# RTI-Dome-Shutter.net
KiCad netlist of a schematic drawn in EAGLE
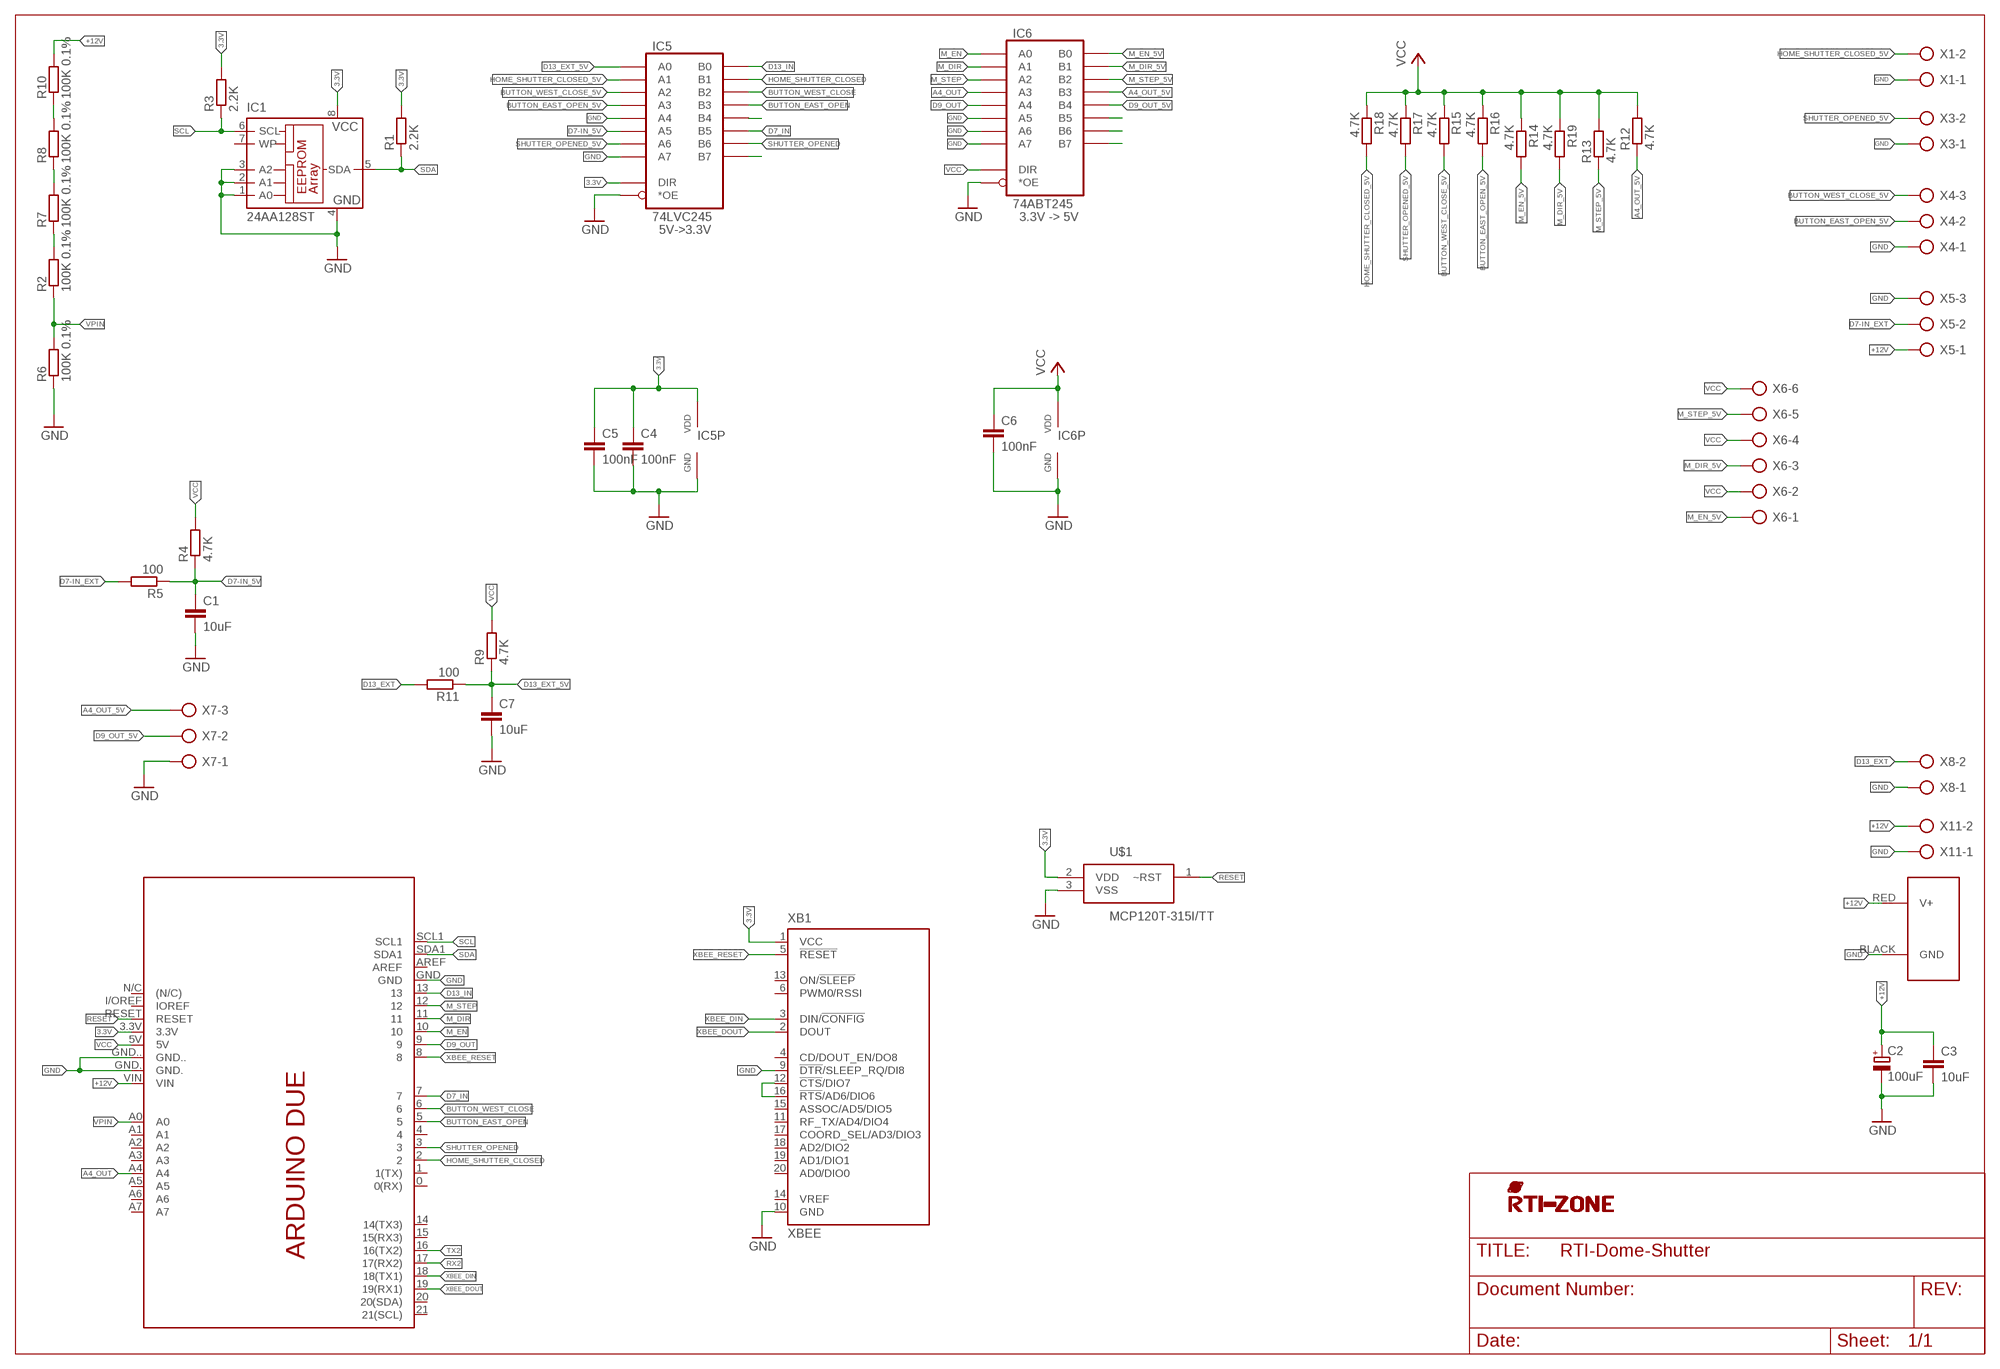
[diagram p0: schematic, sheet 1]

(export (version "E")
  (design (tool "Eeschema 10.0.6"))
  (components
    (comp (ref "C1")
      (value "10uF")
      (footprint "eagle-import:C0805")
      (libsource (lib "eagle-import") (part "C-EU'0805'"))
    )
    (comp (ref "C2")
      (value "100uF")
      (footprint "eagle-import:UD-10X10_NICHICON")
      (libsource (lib "eagle-import") (part "CPOL-EU"))
    )
    (comp (ref "C3")
      (value "10uF")
      (footprint "eagle-import:C0805")
      (libsource (lib "eagle-import") (part "C-EU'0805'"))
    )
    (comp (ref "C4")
      (value "100nF")
      (footprint "eagle-import:C0805")
      (libsource (lib "eagle-import") (part "C-EU'0805'"))
    )
    (comp (ref "C5")
      (value "100nF")
      (footprint "eagle-import:C0805")
      (libsource (lib "eagle-import") (part "C-EU'0805'"))
    )
    (comp (ref "C6")
      (value "100nF")
      (footprint "eagle-import:C0805")
      (libsource (lib "eagle-import") (part "C-EU'0805'"))
    )
    (comp (ref "C7")
      (value "10uF")
      (footprint "eagle-import:C0805")
      (libsource (lib "eagle-import") (part "C-EU'0805'"))
    )
    (comp (ref "IC1")
      (value "24AA128ST")
      (footprint "eagle-import:TSSOP8")
      (fields (field (name "MF") "MICROCHIP") (field (name "MPN") "24AA128-I/ST"))
      (libsource (lib "eagle-import") (part "24STAA128"))
    )
    (comp (ref "IC5")
      (value "74LVC245")
      (footprint "eagle-import:TSSOP20")
      (libsource (lib "eagle-import") (part "74245LVC"))
    )
    (comp (ref "IC6")
      (value "74ABT245")
      (footprint "eagle-import:TSSOP20")
      (libsource (lib "eagle-import") (part "74245ABT"))
    )
    (comp (ref "J1")
      (value "POWERPOLE_POWER45A")
      (footprint "eagle-import:POWERPOLE_PAIR_45A")
      (libsource (lib "eagle-import") (part "POWERPOLE_POWER45A"))
    )
    (comp (ref "PCB1")
      (value "ARDUINO_DUE_SHIELD_SHORT")
      (footprint "eagle-import:ARDUINO_DUE_SHIELD_SHORT")
      (libsource (lib "eagle-import") (part "ARDUINO_DUE_SHIELD_SHORT"))
    )
    (comp (ref "R1")
      (value "2.2K")
      (footprint "eagle-import:R0805")
      (libsource (lib "eagle-import") (part "R-EU'0805'"))
    )
    (comp (ref "R2")
      (value "100K 0.1%")
      (footprint "eagle-import:R0805")
      (libsource (lib "eagle-import") (part "R-EU'0805'"))
    )
    (comp (ref "R3")
      (value "2.2K")
      (footprint "eagle-import:R0805")
      (libsource (lib "eagle-import") (part "R-EU'0805'"))
    )
    (comp (ref "R4")
      (value "4.7K")
      (footprint "eagle-import:R0805")
      (libsource (lib "eagle-import") (part "R-EU'0805'"))
    )
    (comp (ref "R5")
      (value "100")
      (footprint "eagle-import:R0805")
      (libsource (lib "eagle-import") (part "R-EU'0805'"))
    )
    (comp (ref "R6")
      (value "100K 0.1%")
      (footprint "eagle-import:R0805")
      (libsource (lib "eagle-import") (part "R-EU'0805'"))
    )
    (comp (ref "R7")
      (value "100K 0.1%")
      (footprint "eagle-import:R0805")
      (libsource (lib "eagle-import") (part "R-EU'0805'"))
    )
    (comp (ref "R8")
      (value "100K 0.1%")
      (footprint "eagle-import:R0805")
      (libsource (lib "eagle-import") (part "R-EU'0805'"))
    )
    (comp (ref "R9")
      (value "4.7K")
      (footprint "eagle-import:R0805")
      (libsource (lib "eagle-import") (part "R-EU'0805'"))
    )
    (comp (ref "R10")
      (value "100K 0.1%")
      (footprint "eagle-import:R0805")
      (libsource (lib "eagle-import") (part "R-EU'0805'"))
    )
    (comp (ref "R11")
      (value "100")
      (footprint "eagle-import:R0805")
      (libsource (lib "eagle-import") (part "R-EU'0805'"))
    )
    (comp (ref "R12")
      (value "4.7K")
      (footprint "eagle-import:R0805")
      (libsource (lib "eagle-import") (part "R-EU'0805'"))
    )
    (comp (ref "R13")
      (value "4.7K")
      (footprint "eagle-import:R0805")
      (libsource (lib "eagle-import") (part "R-EU'0805'"))
    )
    (comp (ref "R14")
      (value "4.7K")
      (footprint "eagle-import:R0805")
      (libsource (lib "eagle-import") (part "R-EU'0805'"))
    )
    (comp (ref "R15")
      (value "4.7K")
      (footprint "eagle-import:R0805")
      (libsource (lib "eagle-import") (part "R-EU'0805'"))
    )
    (comp (ref "R16")
      (value "4.7K")
      (footprint "eagle-import:R0805")
      (libsource (lib "eagle-import") (part "R-EU'0805'"))
    )
    (comp (ref "R17")
      (value "4.7K")
      (footprint "eagle-import:R0805")
      (libsource (lib "eagle-import") (part "R-EU'0805'"))
    )
    (comp (ref "R18")
      (value "4.7K")
      (footprint "eagle-import:R0805")
      (libsource (lib "eagle-import") (part "R-EU'0805'"))
    )
    (comp (ref "R19")
      (value "4.7K")
      (footprint "eagle-import:R0805")
      (libsource (lib "eagle-import") (part "R-EU'0805'"))
    )
    (comp (ref "U$1")
      (value "MCP120T-315I/TT")
      (footprint "eagle-import:SOT95P237X112-3N")
      (fields (field (name "MOUSER_PART_NUMBER") "579-MCP120T-315I/TT"))
      (libsource (lib "eagle-import") (part "MCP120T"))
    )
    (comp (ref "U$4")
      (value "RTI-LOGO_BIG")
      (footprint "eagle-import:LOGO_BIG")
      (libsource (lib "eagle-import") (part "RTI-LOGO_BIG"))
    )
    (comp (ref "X1")
      (value "AK500/2")
      (footprint "eagle-import:AK500_2")
      (libsource (lib "eagle-import") (part "AK500/2"))
    )
    (comp (ref "X3")
      (value "AK500/2")
      (footprint "eagle-import:AK500_2")
      (libsource (lib "eagle-import") (part "AK500/2"))
    )
    (comp (ref "X4")
      (value "AK500/3")
      (footprint "eagle-import:AK500_3")
      (libsource (lib "eagle-import") (part "AK500/3"))
    )
    (comp (ref "X5")
      (value "AK500/3")
      (footprint "eagle-import:AK500_3")
      (libsource (lib "eagle-import") (part "AK500/3"))
    )
    (comp (ref "X6")
      (value "AK500/6")
      (footprint "eagle-import:AK500_6")
      (libsource (lib "eagle-import") (part "AK500/6"))
    )
    (comp (ref "X7")
      (value "AK500/3")
      (footprint "eagle-import:AK500_3")
      (libsource (lib "eagle-import") (part "AK500/3"))
    )
    (comp (ref "X8")
      (value "AK500/2")
      (footprint "eagle-import:AK500_2")
      (libsource (lib "eagle-import") (part "AK500/2"))
    )
    (comp (ref "X11")
      (value "AK500/2")
      (footprint "eagle-import:AK500_2")
      (libsource (lib "eagle-import") (part "AK500/2"))
    )
    (comp (ref "XB1")
      (value "XBEE")
      (footprint "eagle-import:XBEE")
      (fields (field (name "MPN") "XBP24-Z7UIT-004"))
      (libsource (lib "eagle-import") (part "XBEE"))
    )
  )
  (nets
    (net (code "1") (name "+12V") (class "Default")
      (node (ref "C2") (pin "+") (pinfunction "+_+") (pintype "passive"))
      (node (ref "C3") (pin "1") (pinfunction "1_1") (pintype "passive"))
      (node (ref "J1") (pin "RED") (pinfunction "V+_RED") (pintype "power_in"))
      (node (ref "PCB1") (pin "VIN") (pinfunction "VIN_VIN") (pintype "bidirectional"))
      (node (ref "R10") (pin "2") (pinfunction "2_2") (pintype "passive"))
      (node (ref "X11") (pin "2") (pinfunction "KL_2") (pintype "passive"))
      (node (ref "X5") (pin "1") (pinfunction "KL_1") (pintype "passive"))
    )
    (net (code "2") (name "3.3V") (class "Default")
      (node (ref "C4") (pin "1") (pinfunction "1_1") (pintype "passive"))
      (node (ref "C5") (pin "1") (pinfunction "1_1") (pintype "passive"))
      (node (ref "IC1") (pin "8") (pinfunction "VCC_8") (pintype "power_in"))
      (node (ref "IC5") (pin "P$1") (pinfunction "DIR_P$1") (pintype "input"))
      (node (ref "IC5") (pin "P$20") (pinfunction "VDD_P$20") (pintype "power_in"))
      (node (ref "PCB1") (pin "3.3V") (pinfunction "3.3V_3.3V") (pintype "bidirectional"))
      (node (ref "R1") (pin "2") (pinfunction "2_2") (pintype "passive"))
      (node (ref "R3") (pin "2") (pinfunction "2_2") (pintype "passive"))
      (node (ref "U$1") (pin "2") (pinfunction "VDD_2") (pintype "bidirectional"))
      (node (ref "XB1") (pin "1") (pinfunction "VCC_1") (pintype "power_in"))
    )
    (net (code "3") (name "A4_OUT") (class "Default")
      (node (ref "IC6") (pin "P$5") (pinfunction "A3_P$5") (pintype "bidirectional"))
      (node (ref "PCB1") (pin "A4") (pinfunction "A4_A4") (pintype "bidirectional"))
    )
    (net (code "4") (name "A4_OUT_5V") (class "Default")
      (node (ref "IC6") (pin "P$15") (pinfunction "B3_P$15") (pintype "bidirectional"))
      (node (ref "R12") (pin "1") (pinfunction "1_1") (pintype "passive"))
      (node (ref "X7") (pin "3") (pinfunction "KL_3") (pintype "passive"))
    )
    (net (code "5") (name "BUTTON_EAST_OPEN") (class "Default")
      (node (ref "IC5") (pin "P$15") (pinfunction "B3_P$15") (pintype "bidirectional"))
      (node (ref "PCB1") (pin "5") (pinfunction "5_5") (pintype "bidirectional"))
    )
    (net (code "6") (name "BUTTON_EAST_OPEN_5V") (class "Default")
      (node (ref "IC5") (pin "P$5") (pinfunction "A3_P$5") (pintype "bidirectional"))
      (node (ref "R16") (pin "2") (pinfunction "2_2") (pintype "passive"))
      (node (ref "X4") (pin "2") (pinfunction "KL_2") (pintype "passive"))
    )
    (net (code "7") (name "BUTTON_WEST_CLOSE") (class "Default")
      (node (ref "IC5") (pin "P$16") (pinfunction "B2_P$16") (pintype "bidirectional"))
      (node (ref "PCB1") (pin "6") (pinfunction "6_6") (pintype "bidirectional"))
    )
    (net (code "8") (name "BUTTON_WEST_CLOSE_5V") (class "Default")
      (node (ref "IC5") (pin "P$4") (pinfunction "A2_P$4") (pintype "bidirectional"))
      (node (ref "R15") (pin "2") (pinfunction "2_2") (pintype "passive"))
      (node (ref "X4") (pin "3") (pinfunction "KL_3") (pintype "passive"))
    )
    (net (code "9") (name "D7-IN_5V") (class "Default")
      (node (ref "C1") (pin "1") (pinfunction "1_1") (pintype "passive"))
      (node (ref "IC5") (pin "P$7") (pinfunction "A5_P$7") (pintype "bidirectional"))
      (node (ref "R4") (pin "1") (pinfunction "1_1") (pintype "passive"))
      (node (ref "R5") (pin "1") (pinfunction "1_1") (pintype "passive"))
    )
    (net (code "10") (name "D7-IN_EXT") (class "Default")
      (node (ref "R5") (pin "2") (pinfunction "2_2") (pintype "passive"))
      (node (ref "X5") (pin "2") (pinfunction "KL_2") (pintype "passive"))
    )
    (net (code "11") (name "D7_IN") (class "Default")
      (node (ref "IC5") (pin "P$13") (pinfunction "B5_P$13") (pintype "bidirectional"))
      (node (ref "PCB1") (pin "7") (pinfunction "7_7") (pintype "bidirectional"))
    )
    (net (code "12") (name "D9_OUT") (class "Default")
      (node (ref "IC6") (pin "P$6") (pinfunction "A4_P$6") (pintype "bidirectional"))
      (node (ref "PCB1") (pin "9") (pinfunction "9_9") (pintype "bidirectional"))
    )
    (net (code "13") (name "D9_OUT_5V") (class "Default")
      (node (ref "IC6") (pin "P$14") (pinfunction "B4_P$14") (pintype "bidirectional"))
      (node (ref "X7") (pin "2") (pinfunction "KL_2") (pintype "passive"))
    )
    (net (code "14") (name "D13_EXT") (class "Default")
      (node (ref "R11") (pin "2") (pinfunction "2_2") (pintype "passive"))
      (node (ref "X8") (pin "2") (pinfunction "KL_2") (pintype "passive"))
    )
    (net (code "15") (name "D13_EXT_5V") (class "Default")
      (node (ref "C7") (pin "1") (pinfunction "1_1") (pintype "passive"))
      (node (ref "IC5") (pin "P$2") (pinfunction "A0_P$2") (pintype "bidirectional"))
      (node (ref "R11") (pin "1") (pinfunction "1_1") (pintype "passive"))
      (node (ref "R9") (pin "1") (pinfunction "1_1") (pintype "passive"))
    )
    (net (code "16") (name "D13_IN") (class "Default")
      (node (ref "IC5") (pin "P$18") (pinfunction "B0_P$18") (pintype "bidirectional"))
      (node (ref "PCB1") (pin "13") (pinfunction "13_13") (pintype "bidirectional"))
    )
    (net (code "17") (name "GND") (class "Default")
      (node (ref "C1") (pin "2") (pinfunction "2_2") (pintype "passive"))
      (node (ref "C2") (pin "-") (pinfunction "-_-") (pintype "passive"))
      (node (ref "C3") (pin "2") (pinfunction "2_2") (pintype "passive"))
      (node (ref "C4") (pin "2") (pinfunction "2_2") (pintype "passive"))
      (node (ref "C5") (pin "2") (pinfunction "2_2") (pintype "passive"))
      (node (ref "C6") (pin "2") (pinfunction "2_2") (pintype "passive"))
      (node (ref "C7") (pin "2") (pinfunction "2_2") (pintype "passive"))
      (node (ref "IC1") (pin "1") (pinfunction "A0_1") (pintype "input"))
      (node (ref "IC1") (pin "2") (pinfunction "A1_2") (pintype "input"))
      (node (ref "IC1") (pin "3") (pinfunction "A2_3") (pintype "input"))
      (node (ref "IC1") (pin "4") (pinfunction "GND_4") (pintype "power_in"))
      (node (ref "IC5") (pin "P$10") (pinfunction "GND_P$10") (pintype "power_in"))
      (node (ref "IC5") (pin "P$19") (pinfunction "*OE_P$19") (pintype "input"))
      (node (ref "IC5") (pin "P$6") (pinfunction "A4_P$6") (pintype "bidirectional"))
      (node (ref "IC5") (pin "P$9") (pinfunction "A7_P$9") (pintype "bidirectional"))
      (node (ref "IC6") (pin "P$10") (pinfunction "GND_P$10") (pintype "power_in"))
      (node (ref "IC6") (pin "P$19") (pinfunction "*OE_P$19") (pintype "input"))
      (node (ref "IC6") (pin "P$7") (pinfunction "A5_P$7") (pintype "bidirectional"))
      (node (ref "IC6") (pin "P$8") (pinfunction "A6_P$8") (pintype "bidirectional"))
      (node (ref "IC6") (pin "P$9") (pinfunction "A7_P$9") (pintype "bidirectional"))
      (node (ref "J1") (pin "BLACK") (pinfunction "GND_BLACK") (pintype "power_in"))
      (node (ref "PCB1") (pin "GND") (pinfunction "GND_GND") (pintype "bidirectional"))
      (node (ref "PCB1") (pin "GND.") (pinfunction "GND._GND.") (pintype "bidirectional"))
      (node (ref "PCB1") (pin "GND..") (pinfunction "GND.._GND..") (pintype "bidirectional"))
      (node (ref "R6") (pin "1") (pinfunction "1_1") (pintype "passive"))
      (node (ref "U$1") (pin "3") (pinfunction "VSS_3") (pintype "bidirectional"))
      (node (ref "X1") (pin "1") (pinfunction "KL_1") (pintype "passive"))
      (node (ref "X11") (pin "1") (pinfunction "KL_1") (pintype "passive"))
      (node (ref "X3") (pin "1") (pinfunction "KL_1") (pintype "passive"))
      (node (ref "X4") (pin "1") (pinfunction "KL_1") (pintype "passive"))
      (node (ref "X5") (pin "3") (pinfunction "KL_3") (pintype "passive"))
      (node (ref "X7") (pin "1") (pinfunction "KL_1") (pintype "passive"))
      (node (ref "X8") (pin "1") (pinfunction "KL_1") (pintype "passive"))
      (node (ref "XB1") (pin "10") (pinfunction "GND_10") (pintype "power_in"))
      (node (ref "XB1") (pin "9") (pinfunction "~{DTR}/SLEEP_RQ/DI8_9") (pintype "bidirectional"))
    )
    (net (code "18") (name "HOME_SHUTTER_CLOSED") (class "Default")
      (node (ref "IC5") (pin "P$17") (pinfunction "B1_P$17") (pintype "bidirectional"))
      (node (ref "PCB1") (pin "2") (pinfunction "2_2") (pintype "bidirectional"))
    )
    (net (code "19") (name "HOME_SHUTTER_CLOSED_5V") (class "Default")
      (node (ref "IC5") (pin "P$3") (pinfunction "A1_P$3") (pintype "bidirectional"))
      (node (ref "R18") (pin "2") (pinfunction "2_2") (pintype "passive"))
      (node (ref "X1") (pin "2") (pinfunction "KL_2") (pintype "passive"))
    )
    (net (code "20") (name "M_DIR") (class "Default")
      (node (ref "IC6") (pin "P$3") (pinfunction "A1_P$3") (pintype "bidirectional"))
      (node (ref "PCB1") (pin "11") (pinfunction "11_11") (pintype "bidirectional"))
    )
    (net (code "21") (name "M_DIR_5V") (class "Default")
      (node (ref "IC6") (pin "P$17") (pinfunction "B1_P$17") (pintype "bidirectional"))
      (node (ref "R19") (pin "2") (pinfunction "2_2") (pintype "passive"))
      (node (ref "X6") (pin "3") (pinfunction "KL_3") (pintype "passive"))
    )
    (net (code "22") (name "M_EN") (class "Default")
      (node (ref "IC6") (pin "P$2") (pinfunction "A0_P$2") (pintype "bidirectional"))
      (node (ref "PCB1") (pin "10") (pinfunction "10_10") (pintype "bidirectional"))
    )
    (net (code "23") (name "M_EN_5V") (class "Default")
      (node (ref "IC6") (pin "P$18") (pinfunction "B0_P$18") (pintype "bidirectional"))
      (node (ref "R14") (pin "2") (pinfunction "2_2") (pintype "passive"))
      (node (ref "X6") (pin "1") (pinfunction "KL_1") (pintype "passive"))
    )
    (net (code "24") (name "M_STEP") (class "Default")
      (node (ref "IC6") (pin "P$4") (pinfunction "A2_P$4") (pintype "bidirectional"))
      (node (ref "PCB1") (pin "12") (pinfunction "12_12") (pintype "bidirectional"))
    )
    (net (code "25") (name "M_STEP_5V") (class "Default")
      (node (ref "IC6") (pin "P$16") (pinfunction "B2_P$16") (pintype "bidirectional"))
      (node (ref "R13") (pin "1") (pinfunction "1_1") (pintype "passive"))
      (node (ref "X6") (pin "5") (pinfunction "KL_5") (pintype "passive"))
    )
    (net (code "26") (name "Net-(R2-Pad2)") (class "Default")
      (node (ref "R2") (pin "2") (pinfunction "2_2") (pintype "passive"))
      (node (ref "R7") (pin "1") (pinfunction "1_1") (pintype "passive"))
    )
    (net (code "27") (name "Net-(R7-Pad2)") (class "Default")
      (node (ref "R7") (pin "2") (pinfunction "2_2") (pintype "passive"))
      (node (ref "R8") (pin "1") (pinfunction "1_1") (pintype "passive"))
    )
    (net (code "28") (name "Net-(R10-Pad1)") (class "Default")
      (node (ref "R10") (pin "1") (pinfunction "1_1") (pintype "passive"))
      (node (ref "R8") (pin "2") (pinfunction "2_2") (pintype "passive"))
    )
    (net (code "29") (name "Net-(XB1-~{CTS}{slash}DIO7)") (class "Default")
      (node (ref "XB1") (pin "12") (pinfunction "~{CTS}/DIO7_12") (pintype "bidirectional"))
      (node (ref "XB1") (pin "16") (pinfunction "~{RTS}/AD6/DIO6_16") (pintype "bidirectional"))
    )
    (net (code "30") (name "RESET") (class "Default")
      (node (ref "PCB1") (pin "RESET") (pinfunction "RESET_RESET") (pintype "bidirectional"))
      (node (ref "U$1") (pin "1") (pinfunction "~{RST}_1") (pintype "bidirectional"))
    )
    (net (code "31") (name "RX2") (class "Default")
      (node (ref "PCB1") (pin "17") (pinfunction "17(RX2)_17") (pintype "bidirectional"))
    )
    (net (code "32") (name "SCL") (class "Default")
      (node (ref "IC1") (pin "6") (pinfunction "SCL_6") (pintype "input"))
      (node (ref "PCB1") (pin "SCL1") (pinfunction "SCL1_SCL1") (pintype "bidirectional"))
      (node (ref "R3") (pin "1") (pinfunction "1_1") (pintype "passive"))
    )
    (net (code "33") (name "SDA") (class "Default")
      (node (ref "IC1") (pin "5") (pinfunction "SDA_5") (pintype "bidirectional"))
      (node (ref "PCB1") (pin "SDA1") (pinfunction "SDA1_SDA1") (pintype "bidirectional"))
      (node (ref "R1") (pin "1") (pinfunction "1_1") (pintype "passive"))
    )
    (net (code "34") (name "SHUTTER_OPENED") (class "Default")
      (node (ref "IC5") (pin "P$12") (pinfunction "B6_P$12") (pintype "bidirectional"))
      (node (ref "PCB1") (pin "3") (pinfunction "3_3") (pintype "bidirectional"))
    )
    (net (code "35") (name "SHUTTER_OPENED_5V") (class "Default")
      (node (ref "IC5") (pin "P$8") (pinfunction "A6_P$8") (pintype "bidirectional"))
      (node (ref "R17") (pin "2") (pinfunction "2_2") (pintype "passive"))
      (node (ref "X3") (pin "2") (pinfunction "KL_2") (pintype "passive"))
    )
    (net (code "36") (name "TX2") (class "Default")
      (node (ref "PCB1") (pin "16") (pinfunction "16(TX2)_16") (pintype "bidirectional"))
    )
    (net (code "37") (name "VCC") (class "Default")
      (node (ref "C6") (pin "1") (pinfunction "1_1") (pintype "passive"))
      (node (ref "IC6") (pin "P$1") (pinfunction "DIR_P$1") (pintype "input"))
      (node (ref "IC6") (pin "P$20") (pinfunction "VDD_P$20") (pintype "power_in"))
      (node (ref "PCB1") (pin "5V") (pinfunction "5V_5V") (pintype "bidirectional"))
      (node (ref "R12") (pin "2") (pinfunction "2_2") (pintype "passive"))
      (node (ref "R13") (pin "2") (pinfunction "2_2") (pintype "passive"))
      (node (ref "R14") (pin "1") (pinfunction "1_1") (pintype "passive"))
      (node (ref "R15") (pin "1") (pinfunction "1_1") (pintype "passive"))
      (node (ref "R16") (pin "1") (pinfunction "1_1") (pintype "passive"))
      (node (ref "R17") (pin "1") (pinfunction "1_1") (pintype "passive"))
      (node (ref "R18") (pin "1") (pinfunction "1_1") (pintype "passive"))
      (node (ref "R19") (pin "1") (pinfunction "1_1") (pintype "passive"))
      (node (ref "R4") (pin "2") (pinfunction "2_2") (pintype "passive"))
      (node (ref "R9") (pin "2") (pinfunction "2_2") (pintype "passive"))
      (node (ref "X6") (pin "2") (pinfunction "KL_2") (pintype "passive"))
      (node (ref "X6") (pin "4") (pinfunction "KL_4") (pintype "passive"))
      (node (ref "X6") (pin "6") (pinfunction "KL_6") (pintype "passive"))
    )
    (net (code "38") (name "VPIN") (class "Default")
      (node (ref "PCB1") (pin "A0") (pinfunction "A0_A0") (pintype "bidirectional"))
      (node (ref "R2") (pin "1") (pinfunction "1_1") (pintype "passive"))
      (node (ref "R6") (pin "2") (pinfunction "2_2") (pintype "passive"))
    )
    (net (code "39") (name "XBEE_DIN") (class "Default")
      (node (ref "PCB1") (pin "18") (pinfunction "18(TX1)_18") (pintype "bidirectional"))
      (node (ref "XB1") (pin "3") (pinfunction "DIN/~{CONFIG}_3") (pintype "input"))
    )
    (net (code "40") (name "XBEE_DOUT") (class "Default")
      (node (ref "PCB1") (pin "19") (pinfunction "19(RX1)_19") (pintype "bidirectional"))
      (node (ref "XB1") (pin "2") (pinfunction "DOUT_2") (pintype "output"))
    )
    (net (code "41") (name "XBEE_RESET") (class "Default")
      (node (ref "PCB1") (pin "8") (pinfunction "8_8") (pintype "bidirectional"))
      (node (ref "XB1") (pin "5") (pinfunction "~{RESET}_5") (pintype "input"))
    )
    (net (code "42") (name "unconnected-(IC1-WP-Pad7)") (class "Default")
      (node (ref "IC1") (pin "7") (pinfunction "WP_7") (pintype "input"))
    )
    (net (code "43") (name "unconnected-(IC5A-B4-PadP$14)") (class "Default")
      (node (ref "IC5") (pin "P$14") (pinfunction "B4_P$14") (pintype "bidirectional"))
    )
    (net (code "44") (name "unconnected-(IC5A-B7-PadP$11)") (class "Default")
      (node (ref "IC5") (pin "P$11") (pinfunction "B7_P$11") (pintype "bidirectional"))
    )
    (net (code "45") (name "unconnected-(IC6A-B5-PadP$13)") (class "Default")
      (node (ref "IC6") (pin "P$13") (pinfunction "B5_P$13") (pintype "bidirectional"))
    )
    (net (code "46") (name "unconnected-(IC6A-B6-PadP$12)") (class "Default")
      (node (ref "IC6") (pin "P$12") (pinfunction "B6_P$12") (pintype "bidirectional"))
    )
    (net (code "47") (name "unconnected-(IC6A-B7-PadP$11)") (class "Default")
      (node (ref "IC6") (pin "P$11") (pinfunction "B7_P$11") (pintype "bidirectional"))
    )
    (net (code "48") (name "unconnected-(PCB1-(N{slash}C)-PadN{slash}C)") (class "Default")
      (node (ref "PCB1") (pin "N/C") (pinfunction "(N/C)_N/C") (pintype "bidirectional"))
    )
    (net (code "49") (name "unconnected-(PCB1-0(RX)-Pad0)") (class "Default")
      (node (ref "PCB1") (pin "0") (pinfunction "0(RX)_0") (pintype "bidirectional"))
    )
    (net (code "50") (name "unconnected-(PCB1-1(TX)-Pad1)") (class "Default")
      (node (ref "PCB1") (pin "1") (pinfunction "1(TX)_1") (pintype "bidirectional"))
    )
    (net (code "51") (name "unconnected-(PCB1-14(TX3)-Pad14)") (class "Default")
      (node (ref "PCB1") (pin "14") (pinfunction "14(TX3)_14") (pintype "bidirectional"))
    )
    (net (code "52") (name "unconnected-(PCB1-15(RX3)-Pad15)") (class "Default")
      (node (ref "PCB1") (pin "15") (pinfunction "15(RX3)_15") (pintype "bidirectional"))
    )
    (net (code "53") (name "unconnected-(PCB1-20(SDA)-Pad20)") (class "Default")
      (node (ref "PCB1") (pin "20") (pinfunction "20(SDA)_20") (pintype "bidirectional"))
    )
    (net (code "54") (name "unconnected-(PCB1-21(SCL)-Pad21)") (class "Default")
      (node (ref "PCB1") (pin "21") (pinfunction "21(SCL)_21") (pintype "bidirectional"))
    )
    (net (code "55") (name "unconnected-(PCB1-IOREF-PadI{slash}OREF)") (class "Default")
      (node (ref "PCB1") (pin "I/OREF") (pinfunction "IOREF_I/OREF") (pintype "bidirectional"))
    )
    (net (code "56") (name "unconnected-(PCB1-Pad4)") (class "Default")
      (node (ref "PCB1") (pin "4") (pinfunction "4_4") (pintype "bidirectional"))
    )
    (net (code "57") (name "unconnected-(PCB1-PadA1)") (class "Default")
      (node (ref "PCB1") (pin "A1") (pinfunction "A1_A1") (pintype "bidirectional"))
    )
    (net (code "58") (name "unconnected-(PCB1-PadA2)") (class "Default")
      (node (ref "PCB1") (pin "A2") (pinfunction "A2_A2") (pintype "bidirectional"))
    )
    (net (code "59") (name "unconnected-(PCB1-PadA3)") (class "Default")
      (node (ref "PCB1") (pin "A3") (pinfunction "A3_A3") (pintype "bidirectional"))
    )
    (net (code "60") (name "unconnected-(PCB1-PadA5)") (class "Default")
      (node (ref "PCB1") (pin "A5") (pinfunction "A5_A5") (pintype "bidirectional"))
    )
    (net (code "61") (name "unconnected-(PCB1-PadA6)") (class "Default")
      (node (ref "PCB1") (pin "A6") (pinfunction "A6_A6") (pintype "bidirectional"))
    )
    (net (code "62") (name "unconnected-(PCB1-PadA7)") (class "Default")
      (node (ref "PCB1") (pin "A7") (pinfunction "A7_A7") (pintype "bidirectional"))
    )
    (net (code "63") (name "unconnected-(PCB1-PadAREF)") (class "Default")
      (node (ref "PCB1") (pin "AREF") (pinfunction "AREF_AREF") (pintype "bidirectional"))
    )
    (net (code "64") (name "unconnected-(XB1-AD0{slash}DIO0-Pad20)") (class "Default")
      (node (ref "XB1") (pin "20") (pinfunction "AD0/DIO0_20") (pintype "bidirectional"))
    )
    (net (code "65") (name "unconnected-(XB1-AD1{slash}DIO1-Pad19)") (class "Default")
      (node (ref "XB1") (pin "19") (pinfunction "AD1/DIO1_19") (pintype "bidirectional"))
    )
    (net (code "66") (name "unconnected-(XB1-AD2{slash}DIO2-Pad18)") (class "Default")
      (node (ref "XB1") (pin "18") (pinfunction "AD2/DIO2_18") (pintype "bidirectional"))
    )
    (net (code "67") (name "unconnected-(XB1-ASSOC{slash}AD5{slash}DIO5-Pad15)") (class "Default")
      (node (ref "XB1") (pin "15") (pinfunction "ASSOC/AD5/DIO5_15") (pintype "bidirectional"))
    )
    (net (code "68") (name "unconnected-(XB1-CD{slash}DOUT_EN{slash}DO8-Pad4)") (class "Default")
      (node (ref "XB1") (pin "4") (pinfunction "CD/DOUT_EN/DO8_4") (pintype "output"))
    )
    (net (code "69") (name "unconnected-(XB1-COORD_SEL{slash}AD3{slash}DIO3-Pad17)") (class "Default")
      (node (ref "XB1") (pin "17") (pinfunction "COORD_SEL/AD3/DIO3_17") (pintype "bidirectional"))
    )
    (net (code "70") (name "unconnected-(XB1-ON{slash}~{SLEEP}-Pad13)") (class "Default")
      (node (ref "XB1") (pin "13") (pinfunction "ON/~{SLEEP}_13") (pintype "output"))
    )
    (net (code "71") (name "unconnected-(XB1-PWM0{slash}RSSI-Pad6)") (class "Default")
      (node (ref "XB1") (pin "6") (pinfunction "PWM0/RSSI_6") (pintype "output"))
    )
    (net (code "72") (name "unconnected-(XB1-RF_TX{slash}AD4{slash}DIO4-Pad11)") (class "Default")
      (node (ref "XB1") (pin "11") (pinfunction "RF_TX/AD4/DIO4_11") (pintype "bidirectional"))
    )
    (net (code "73") (name "unconnected-(XB1-VREF-Pad14)") (class "Default")
      (node (ref "XB1") (pin "14") (pinfunction "VREF_14") (pintype "input"))
    )
  )
)
